# 180_schematic_5_layer.net
KiCad netlist of a schematic drawn in EAGLE
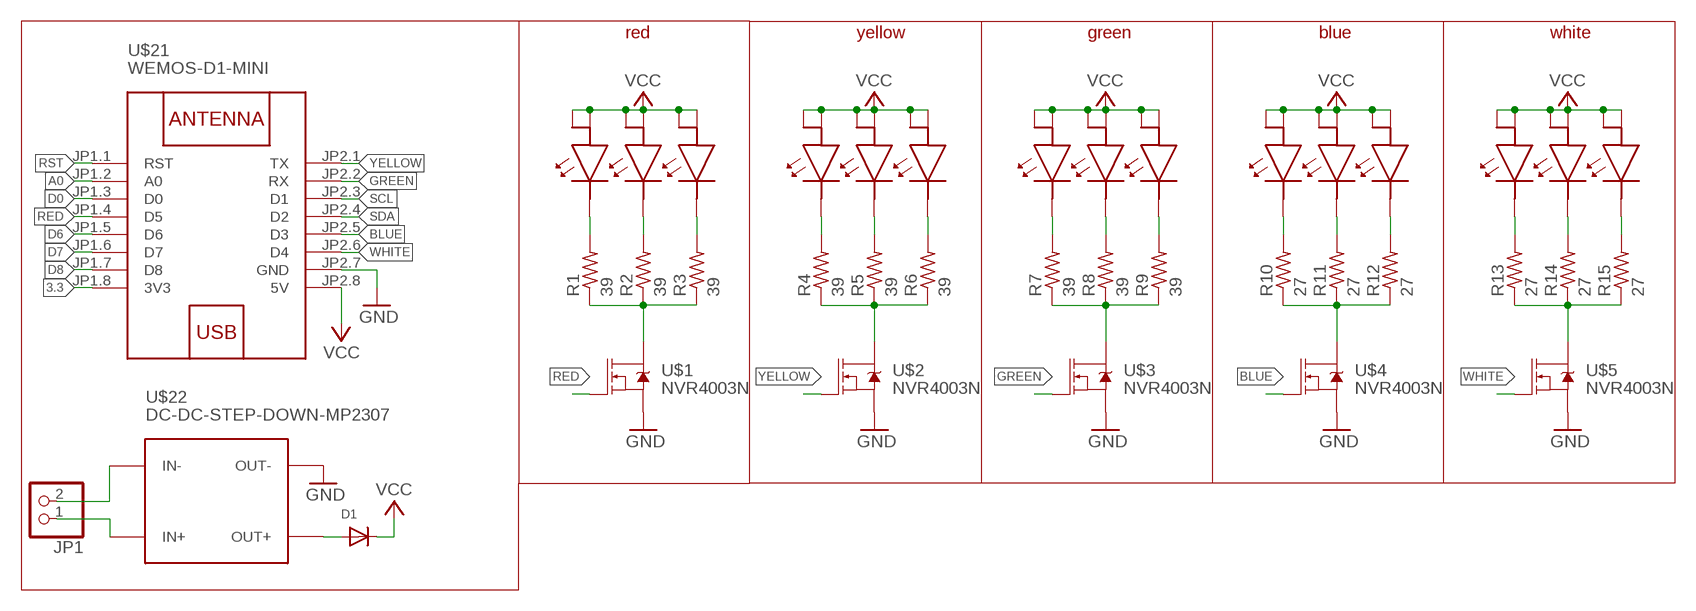
[diagram p0: schematic, sheet 1]

(export (version "E")
  (design (tool "Eeschema 10.0.6"))
  (components
    (comp (ref "D1")
      (value "DIODESOD-123")
      (footprint "eagle-import:SOD-123")
      (libsource (lib "eagle-import") (part "DIODESOD-123"))
    )
    (comp (ref "JP1")
      (value "PINHD-1X2")
      (footprint "eagle-import:1X02")
      (libsource (lib "eagle-import") (part "PINHD-1X2"))
    )
    (comp (ref "R1")
      (value "39")
      (footprint "eagle-import:R1206W")
      (libsource (lib "eagle-import") (part "R-US_R1206W"))
    )
    (comp (ref "R2")
      (value "39")
      (footprint "eagle-import:R1206W")
      (libsource (lib "eagle-import") (part "R-US_R1206W"))
    )
    (comp (ref "R3")
      (value "39")
      (footprint "eagle-import:R1206W")
      (libsource (lib "eagle-import") (part "R-US_R1206W"))
    )
    (comp (ref "R4")
      (value "39")
      (footprint "eagle-import:R1206W")
      (libsource (lib "eagle-import") (part "R-US_R1206W"))
    )
    (comp (ref "R5")
      (value "39")
      (footprint "eagle-import:R1206W")
      (libsource (lib "eagle-import") (part "R-US_R1206W"))
    )
    (comp (ref "R6")
      (value "39")
      (footprint "eagle-import:R1206W")
      (libsource (lib "eagle-import") (part "R-US_R1206W"))
    )
    (comp (ref "R7")
      (value "39")
      (footprint "eagle-import:R1206W")
      (libsource (lib "eagle-import") (part "R-US_R1206W"))
    )
    (comp (ref "R8")
      (value "39")
      (footprint "eagle-import:R1206W")
      (libsource (lib "eagle-import") (part "R-US_R1206W"))
    )
    (comp (ref "R9")
      (value "39")
      (footprint "eagle-import:R1206W")
      (libsource (lib "eagle-import") (part "R-US_R1206W"))
    )
    (comp (ref "R10")
      (value "27")
      (footprint "eagle-import:R1206W")
      (libsource (lib "eagle-import") (part "R-US_R1206W"))
    )
    (comp (ref "R11")
      (value "27")
      (footprint "eagle-import:R1206W")
      (libsource (lib "eagle-import") (part "R-US_R1206W"))
    )
    (comp (ref "R12")
      (value "27")
      (footprint "eagle-import:R1206W")
      (libsource (lib "eagle-import") (part "R-US_R1206W"))
    )
    (comp (ref "R13")
      (value "27")
      (footprint "eagle-import:R1206W")
      (libsource (lib "eagle-import") (part "R-US_R1206W"))
    )
    (comp (ref "R14")
      (value "27")
      (footprint "eagle-import:R1206W")
      (libsource (lib "eagle-import") (part "R-US_R1206W"))
    )
    (comp (ref "R15")
      (value "27")
      (footprint "eagle-import:R1206W")
      (libsource (lib "eagle-import") (part "R-US_R1206W"))
    )
    (comp (ref "U$1")
      (value "NVR4003N")
      (footprint "eagle-import:SOT23")
      (libsource (lib "eagle-import") (part "NVR4003N"))
    )
    (comp (ref "U$2")
      (value "NVR4003N")
      (footprint "eagle-import:SOT23")
      (libsource (lib "eagle-import") (part "NVR4003N"))
    )
    (comp (ref "U$3")
      (value "NVR4003N")
      (footprint "eagle-import:SOT23")
      (libsource (lib "eagle-import") (part "NVR4003N"))
    )
    (comp (ref "U$4")
      (value "NVR4003N")
      (footprint "eagle-import:SOT23")
      (libsource (lib "eagle-import") (part "NVR4003N"))
    )
    (comp (ref "U$5")
      (value "NVR4003N")
      (footprint "eagle-import:SOT23")
      (libsource (lib "eagle-import") (part "NVR4003N"))
    )
    (comp (ref "U$6")
      (value "5730LED")
      (footprint "eagle-import:5730LED")
      (libsource (lib "eagle-import") (part "5730LED"))
    )
    (comp (ref "U$7")
      (value "5730LED")
      (footprint "eagle-import:5730LED")
      (libsource (lib "eagle-import") (part "5730LED"))
    )
    (comp (ref "U$8")
      (value "5730LED")
      (footprint "eagle-import:5730LED")
      (libsource (lib "eagle-import") (part "5730LED"))
    )
    (comp (ref "U$9")
      (value "5730LED")
      (footprint "eagle-import:5730LED")
      (libsource (lib "eagle-import") (part "5730LED"))
    )
    (comp (ref "U$10")
      (value "5730LED")
      (footprint "eagle-import:5730LED")
      (libsource (lib "eagle-import") (part "5730LED"))
    )
    (comp (ref "U$11")
      (value "5730LED")
      (footprint "eagle-import:5730LED")
      (libsource (lib "eagle-import") (part "5730LED"))
    )
    (comp (ref "U$12")
      (value "5730LED")
      (footprint "eagle-import:5730LED")
      (libsource (lib "eagle-import") (part "5730LED"))
    )
    (comp (ref "U$13")
      (value "5730LED")
      (footprint "eagle-import:5730LED")
      (libsource (lib "eagle-import") (part "5730LED"))
    )
    (comp (ref "U$14")
      (value "5730LED")
      (footprint "eagle-import:5730LED")
      (libsource (lib "eagle-import") (part "5730LED"))
    )
    (comp (ref "U$15")
      (value "5730LED")
      (footprint "eagle-import:5730LED")
      (libsource (lib "eagle-import") (part "5730LED"))
    )
    (comp (ref "U$16")
      (value "5730LED")
      (footprint "eagle-import:5730LED")
      (libsource (lib "eagle-import") (part "5730LED"))
    )
    (comp (ref "U$17")
      (value "5730LED")
      (footprint "eagle-import:5730LED")
      (libsource (lib "eagle-import") (part "5730LED"))
    )
    (comp (ref "U$18")
      (value "5730LED")
      (footprint "eagle-import:5730LED")
      (libsource (lib "eagle-import") (part "5730LED"))
    )
    (comp (ref "U$19")
      (value "5730LED")
      (footprint "eagle-import:5730LED")
      (libsource (lib "eagle-import") (part "5730LED"))
    )
    (comp (ref "U$20")
      (value "5730LED")
      (footprint "eagle-import:5730LED")
      (libsource (lib "eagle-import") (part "5730LED"))
    )
    (comp (ref "U$21")
      (value "WEMOS-D1-MINI")
      (footprint "eagle-import:WEMOS-D1-MINI")
      (libsource (lib "eagle-import") (part "WEMOS-D1-MINI"))
    )
    (comp (ref "U$22")
      (value "DC-DC-STEP-DOWN-MP2307")
      (footprint "eagle-import:DC-DC-STEP-DOWN-MP2307")
      (libsource (lib "eagle-import") (part "DC-DC-STEP-DOWN-MP2307"))
    )
  )
  (nets
    (net (code "1") (name "3.3") (class "Default")
      (node (ref "U$21") (pin "JP1.8") (pinfunction "3V3_JP1.8") (pintype "power_in"))
    )
    (net (code "2") (name "A0") (class "Default")
      (node (ref "U$21") (pin "JP1.2") (pinfunction "A0_JP1.2") (pintype "bidirectional"))
    )
    (net (code "3") (name "BLUE") (class "Default")
      (node (ref "U$21") (pin "JP2.5") (pinfunction "D3_JP2.5") (pintype "bidirectional"))
      (node (ref "U$4") (pin "2") (pinfunction "G_2") (pintype "bidirectional"))
    )
    (net (code "4") (name "D0") (class "Default")
      (node (ref "U$21") (pin "JP1.3") (pinfunction "D0_JP1.3") (pintype "bidirectional"))
    )
    (net (code "5") (name "D6") (class "Default")
      (node (ref "U$21") (pin "JP1.5") (pinfunction "D6_JP1.5") (pintype "bidirectional"))
    )
    (net (code "6") (name "D7") (class "Default")
      (node (ref "U$21") (pin "JP1.6") (pinfunction "D7_JP1.6") (pintype "bidirectional"))
    )
    (net (code "7") (name "D8") (class "Default")
      (node (ref "U$21") (pin "JP1.7") (pinfunction "D8_JP1.7") (pintype "bidirectional"))
    )
    (net (code "8") (name "GND") (class "Default")
      (node (ref "U$1") (pin "3") (pinfunction "S_3") (pintype "bidirectional"))
      (node (ref "U$2") (pin "3") (pinfunction "S_3") (pintype "bidirectional"))
      (node (ref "U$21") (pin "JP2.7") (pinfunction "GND_JP2.7") (pintype "power_in"))
      (node (ref "U$22") (pin "OUT-") (pinfunction "OUT-_OUT-") (pintype "bidirectional"))
      (node (ref "U$3") (pin "3") (pinfunction "S_3") (pintype "bidirectional"))
      (node (ref "U$4") (pin "3") (pinfunction "S_3") (pintype "bidirectional"))
      (node (ref "U$5") (pin "3") (pinfunction "S_3") (pintype "bidirectional"))
    )
    (net (code "9") (name "GREEN") (class "Default")
      (node (ref "U$21") (pin "JP2.2") (pinfunction "RX_JP2.2") (pintype "bidirectional"))
      (node (ref "U$3") (pin "2") (pinfunction "G_2") (pintype "bidirectional"))
    )
    (net (code "10") (name "Net-(D1-PadA)") (class "Default")
      (node (ref "D1") (pin "A") (pinfunction "A_A") (pintype "passive"))
      (node (ref "U$22") (pin "OUT+") (pinfunction "OUT+_OUT+") (pintype "bidirectional"))
    )
    (net (code "11") (name "Net-(JP1-Pad1)") (class "Default")
      (node (ref "JP1") (pin "1") (pinfunction "1_1") (pintype "passive"))
      (node (ref "U$22") (pin "IN+") (pinfunction "IN+_IN+") (pintype "bidirectional"))
    )
    (net (code "12") (name "Net-(JP1-Pad2)") (class "Default")
      (node (ref "JP1") (pin "2") (pinfunction "2_2") (pintype "passive"))
      (node (ref "U$22") (pin "IN-") (pinfunction "IN-_IN-") (pintype "bidirectional"))
    )
    (net (code "13") (name "Net-(R1-Pad2)") (class "Default")
      (node (ref "R1") (pin "2") (pinfunction "2_2") (pintype "passive"))
      (node (ref "U$6") (pin "P$2") (pinfunction "P$2_P$2") (pintype "bidirectional"))
    )
    (net (code "14") (name "Net-(R2-Pad2)") (class "Default")
      (node (ref "R2") (pin "2") (pinfunction "2_2") (pintype "passive"))
      (node (ref "U$7") (pin "P$2") (pinfunction "P$2_P$2") (pintype "bidirectional"))
    )
    (net (code "15") (name "Net-(R3-Pad2)") (class "Default")
      (node (ref "R3") (pin "2") (pinfunction "2_2") (pintype "passive"))
      (node (ref "U$8") (pin "P$2") (pinfunction "P$2_P$2") (pintype "bidirectional"))
    )
    (net (code "16") (name "Net-(R4-Pad2)") (class "Default")
      (node (ref "R4") (pin "2") (pinfunction "2_2") (pintype "passive"))
      (node (ref "U$9") (pin "P$2") (pinfunction "P$2_P$2") (pintype "bidirectional"))
    )
    (net (code "17") (name "Net-(R5-Pad2)") (class "Default")
      (node (ref "R5") (pin "2") (pinfunction "2_2") (pintype "passive"))
      (node (ref "U$10") (pin "P$2") (pinfunction "P$2_P$2") (pintype "bidirectional"))
    )
    (net (code "18") (name "Net-(R6-Pad2)") (class "Default")
      (node (ref "R6") (pin "2") (pinfunction "2_2") (pintype "passive"))
      (node (ref "U$11") (pin "P$2") (pinfunction "P$2_P$2") (pintype "bidirectional"))
    )
    (net (code "19") (name "Net-(R7-Pad2)") (class "Default")
      (node (ref "R7") (pin "2") (pinfunction "2_2") (pintype "passive"))
      (node (ref "U$12") (pin "P$2") (pinfunction "P$2_P$2") (pintype "bidirectional"))
    )
    (net (code "20") (name "Net-(R8-Pad2)") (class "Default")
      (node (ref "R8") (pin "2") (pinfunction "2_2") (pintype "passive"))
      (node (ref "U$13") (pin "P$2") (pinfunction "P$2_P$2") (pintype "bidirectional"))
    )
    (net (code "21") (name "Net-(R9-Pad2)") (class "Default")
      (node (ref "R9") (pin "2") (pinfunction "2_2") (pintype "passive"))
      (node (ref "U$14") (pin "P$2") (pinfunction "P$2_P$2") (pintype "bidirectional"))
    )
    (net (code "22") (name "Net-(R10-Pad2)") (class "Default")
      (node (ref "R10") (pin "2") (pinfunction "2_2") (pintype "passive"))
      (node (ref "U$15") (pin "P$2") (pinfunction "P$2_P$2") (pintype "bidirectional"))
    )
    (net (code "23") (name "Net-(R11-Pad2)") (class "Default")
      (node (ref "R11") (pin "2") (pinfunction "2_2") (pintype "passive"))
      (node (ref "U$16") (pin "P$2") (pinfunction "P$2_P$2") (pintype "bidirectional"))
    )
    (net (code "24") (name "Net-(R12-Pad2)") (class "Default")
      (node (ref "R12") (pin "2") (pinfunction "2_2") (pintype "passive"))
      (node (ref "U$17") (pin "P$2") (pinfunction "P$2_P$2") (pintype "bidirectional"))
    )
    (net (code "25") (name "Net-(R13-Pad2)") (class "Default")
      (node (ref "R13") (pin "2") (pinfunction "2_2") (pintype "passive"))
      (node (ref "U$18") (pin "P$2") (pinfunction "P$2_P$2") (pintype "bidirectional"))
    )
    (net (code "26") (name "Net-(R14-Pad2)") (class "Default")
      (node (ref "R14") (pin "2") (pinfunction "2_2") (pintype "passive"))
      (node (ref "U$19") (pin "P$2") (pinfunction "P$2_P$2") (pintype "bidirectional"))
    )
    (net (code "27") (name "Net-(R15-Pad2)") (class "Default")
      (node (ref "R15") (pin "2") (pinfunction "2_2") (pintype "passive"))
      (node (ref "U$20") (pin "P$2") (pinfunction "P$2_P$2") (pintype "bidirectional"))
    )
    (net (code "28") (name "Net-(U$1-D)") (class "Default")
      (node (ref "R1") (pin "1") (pinfunction "1_1") (pintype "passive"))
      (node (ref "R2") (pin "1") (pinfunction "1_1") (pintype "passive"))
      (node (ref "R3") (pin "1") (pinfunction "1_1") (pintype "passive"))
      (node (ref "U$1") (pin "1") (pinfunction "D_1") (pintype "bidirectional"))
    )
    (net (code "29") (name "Net-(U$2-D)") (class "Default")
      (node (ref "R4") (pin "1") (pinfunction "1_1") (pintype "passive"))
      (node (ref "R5") (pin "1") (pinfunction "1_1") (pintype "passive"))
      (node (ref "R6") (pin "1") (pinfunction "1_1") (pintype "passive"))
      (node (ref "U$2") (pin "1") (pinfunction "D_1") (pintype "bidirectional"))
    )
    (net (code "30") (name "Net-(U$3-D)") (class "Default")
      (node (ref "R7") (pin "1") (pinfunction "1_1") (pintype "passive"))
      (node (ref "R8") (pin "1") (pinfunction "1_1") (pintype "passive"))
      (node (ref "R9") (pin "1") (pinfunction "1_1") (pintype "passive"))
      (node (ref "U$3") (pin "1") (pinfunction "D_1") (pintype "bidirectional"))
    )
    (net (code "31") (name "Net-(U$4-D)") (class "Default")
      (node (ref "R10") (pin "1") (pinfunction "1_1") (pintype "passive"))
      (node (ref "R11") (pin "1") (pinfunction "1_1") (pintype "passive"))
      (node (ref "R12") (pin "1") (pinfunction "1_1") (pintype "passive"))
      (node (ref "U$4") (pin "1") (pinfunction "D_1") (pintype "bidirectional"))
    )
    (net (code "32") (name "Net-(U$5-D)") (class "Default")
      (node (ref "R13") (pin "1") (pinfunction "1_1") (pintype "passive"))
      (node (ref "R14") (pin "1") (pinfunction "1_1") (pintype "passive"))
      (node (ref "R15") (pin "1") (pinfunction "1_1") (pintype "passive"))
      (node (ref "U$5") (pin "1") (pinfunction "D_1") (pintype "bidirectional"))
    )
    (net (code "33") (name "RED") (class "Default")
      (node (ref "U$1") (pin "2") (pinfunction "G_2") (pintype "bidirectional"))
      (node (ref "U$21") (pin "JP1.4") (pinfunction "D5_JP1.4") (pintype "bidirectional"))
    )
    (net (code "34") (name "RST") (class "Default")
      (node (ref "U$21") (pin "JP1.1") (pinfunction "RST_JP1.1") (pintype "bidirectional"))
    )
    (net (code "35") (name "SCL") (class "Default")
      (node (ref "U$21") (pin "JP2.3") (pinfunction "D1_JP2.3") (pintype "bidirectional"))
    )
    (net (code "36") (name "SDA") (class "Default")
      (node (ref "U$21") (pin "JP2.4") (pinfunction "D2_JP2.4") (pintype "bidirectional"))
    )
    (net (code "37") (name "VCC") (class "Default")
      (node (ref "D1") (pin "C") (pinfunction "C_C") (pintype "passive"))
      (node (ref "U$10") (pin "P$1") (pinfunction "P$1_P$1") (pintype "bidirectional"))
      (node (ref "U$10") (pin "P$3") (pinfunction "P$3_P$3") (pintype "bidirectional"))
      (node (ref "U$11") (pin "P$1") (pinfunction "P$1_P$1") (pintype "bidirectional"))
      (node (ref "U$11") (pin "P$3") (pinfunction "P$3_P$3") (pintype "bidirectional"))
      (node (ref "U$12") (pin "P$1") (pinfunction "P$1_P$1") (pintype "bidirectional"))
      (node (ref "U$12") (pin "P$3") (pinfunction "P$3_P$3") (pintype "bidirectional"))
      (node (ref "U$13") (pin "P$1") (pinfunction "P$1_P$1") (pintype "bidirectional"))
      (node (ref "U$13") (pin "P$3") (pinfunction "P$3_P$3") (pintype "bidirectional"))
      (node (ref "U$14") (pin "P$1") (pinfunction "P$1_P$1") (pintype "bidirectional"))
      (node (ref "U$14") (pin "P$3") (pinfunction "P$3_P$3") (pintype "bidirectional"))
      (node (ref "U$15") (pin "P$1") (pinfunction "P$1_P$1") (pintype "bidirectional"))
      (node (ref "U$15") (pin "P$3") (pinfunction "P$3_P$3") (pintype "bidirectional"))
      (node (ref "U$16") (pin "P$1") (pinfunction "P$1_P$1") (pintype "bidirectional"))
      (node (ref "U$16") (pin "P$3") (pinfunction "P$3_P$3") (pintype "bidirectional"))
      (node (ref "U$17") (pin "P$1") (pinfunction "P$1_P$1") (pintype "bidirectional"))
      (node (ref "U$17") (pin "P$3") (pinfunction "P$3_P$3") (pintype "bidirectional"))
      (node (ref "U$18") (pin "P$1") (pinfunction "P$1_P$1") (pintype "bidirectional"))
      (node (ref "U$18") (pin "P$3") (pinfunction "P$3_P$3") (pintype "bidirectional"))
      (node (ref "U$19") (pin "P$1") (pinfunction "P$1_P$1") (pintype "bidirectional"))
      (node (ref "U$19") (pin "P$3") (pinfunction "P$3_P$3") (pintype "bidirectional"))
      (node (ref "U$20") (pin "P$1") (pinfunction "P$1_P$1") (pintype "bidirectional"))
      (node (ref "U$20") (pin "P$3") (pinfunction "P$3_P$3") (pintype "bidirectional"))
      (node (ref "U$21") (pin "JP2.8") (pinfunction "5V_JP2.8") (pintype "power_in"))
      (node (ref "U$6") (pin "P$1") (pinfunction "P$1_P$1") (pintype "bidirectional"))
      (node (ref "U$6") (pin "P$3") (pinfunction "P$3_P$3") (pintype "bidirectional"))
      (node (ref "U$7") (pin "P$1") (pinfunction "P$1_P$1") (pintype "bidirectional"))
      (node (ref "U$7") (pin "P$3") (pinfunction "P$3_P$3") (pintype "bidirectional"))
      (node (ref "U$8") (pin "P$1") (pinfunction "P$1_P$1") (pintype "bidirectional"))
      (node (ref "U$8") (pin "P$3") (pinfunction "P$3_P$3") (pintype "bidirectional"))
      (node (ref "U$9") (pin "P$1") (pinfunction "P$1_P$1") (pintype "bidirectional"))
      (node (ref "U$9") (pin "P$3") (pinfunction "P$3_P$3") (pintype "bidirectional"))
    )
    (net (code "38") (name "WHITE") (class "Default")
      (node (ref "U$21") (pin "JP2.6") (pinfunction "D4_JP2.6") (pintype "bidirectional"))
      (node (ref "U$5") (pin "2") (pinfunction "G_2") (pintype "bidirectional"))
    )
    (net (code "39") (name "YELLOW") (class "Default")
      (node (ref "U$2") (pin "2") (pinfunction "G_2") (pintype "bidirectional"))
      (node (ref "U$21") (pin "JP2.1") (pinfunction "TX_JP2.1") (pintype "bidirectional"))
    )
  )
)
